# Buck_Converter_Board.net
KiCad netlist of a schematic drawn in EAGLE
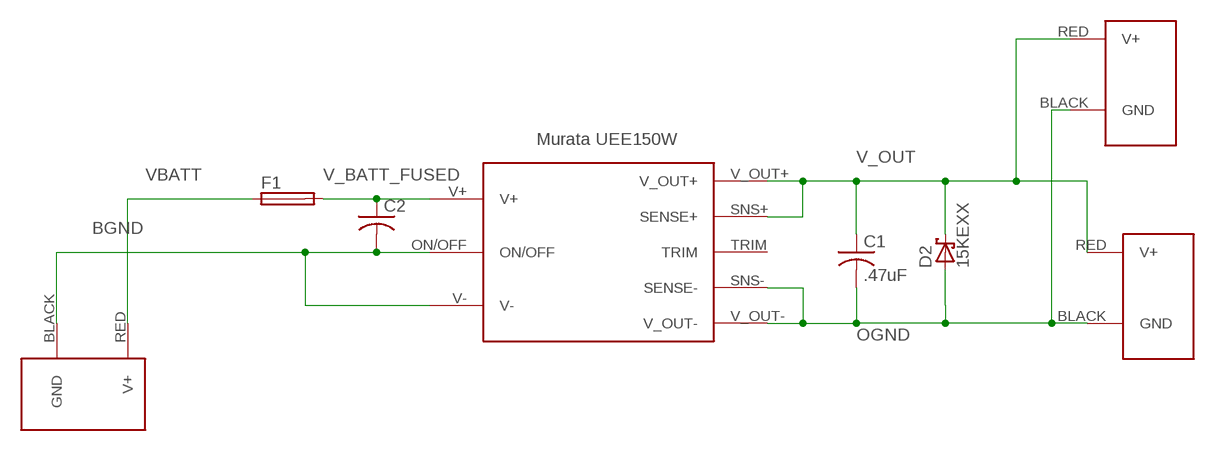
[diagram p0: schematic, sheet 1]

(export (version "E")
  (design (tool "Eeschema 10.0.6"))
  (components
    (comp (ref "C1")
      (value ".47uF")
      (footprint "eagle-import:C0805")
      (libsource (lib "eagle-import") (part "C-USC0805"))
    )
    (comp (ref "C2")
      (value "C-USC0805")
      (footprint "eagle-import:C0805")
      (libsource (lib "eagle-import") (part "C-USC0805"))
    )
    (comp (ref "D2")
      (value "15KEXX")
      (footprint "eagle-import:CB429-17")
      (libsource (lib "eagle-import") (part "15KEXX"))
    )
    (comp (ref "F1")
      (value "FUSEBLANK_5X20MM")
      (footprint "eagle-import:FUSE_HOLDER_5X20MM")
      (libsource (lib "eagle-import") (part "FUSEBLANK_5X20MM"))
    )
    (comp (ref "J1")
      (value "POWERPOLE_POWER25A_HORIZONTAL_G2")
      (footprint "eagle-import:POWERPOLE_PAIR_25A_HORIZ_G2")
      (libsource (lib "eagle-import") (part "POWERPOLE_POWER25A_HORIZONTAL_G2"))
    )
    (comp (ref "J2")
      (value "POWERPOLE_POWER25A_HORIZONTAL_G2")
      (footprint "eagle-import:POWERPOLE_PAIR_25A_HORIZ_G2")
      (libsource (lib "eagle-import") (part "POWERPOLE_POWER25A_HORIZONTAL_G2"))
    )
    (comp (ref "J3")
      (value "POWERPOLE_POWER25A_HORIZONTAL_G2")
      (footprint "eagle-import:POWERPOLE_PAIR_25A_HORIZ_G2")
      (libsource (lib "eagle-import") (part "POWERPOLE_POWER25A_HORIZONTAL_G2"))
    )
    (comp (ref "UEE150W")
      (value "UEE150W")
      (footprint "eagle-import:DOSA1_8")
      (libsource (lib "eagle-import") (part "UEE150W"))
    )
  )
  (nets
    (net (code "1") (name "/BGND") (class "Default")
      (node (ref "C2") (pin "2") (pinfunction "2_2") (pintype "passive"))
      (node (ref "J1") (pin "BLACK") (pinfunction "GND_BLACK") (pintype "power_in"))
      (node (ref "UEE150W") (pin "ON/OFF") (pinfunction "ON/OFF_ON/OFF") (pintype "input"))
      (node (ref "UEE150W") (pin "V-") (pinfunction "V-_V-") (pintype "power_in"))
    )
    (net (code "2") (name "/OGND") (class "Default")
      (node (ref "C1") (pin "2") (pinfunction "2_2") (pintype "passive"))
      (node (ref "D2") (pin "A") (pinfunction "A_A") (pintype "passive"))
      (node (ref "J2") (pin "BLACK") (pinfunction "GND_BLACK") (pintype "power_in"))
      (node (ref "J3") (pin "BLACK") (pinfunction "GND_BLACK") (pintype "power_in"))
      (node (ref "UEE150W") (pin "SNS-") (pinfunction "SENSE-_SNS-") (pintype "bidirectional"))
      (node (ref "UEE150W") (pin "V_OUT-") (pinfunction "V_OUT-_V_OUT-") (pintype "output"))
    )
    (net (code "3") (name "/VBATT") (class "Default")
      (node (ref "F1") (pin "1") (pinfunction "1_1") (pintype "passive"))
      (node (ref "J1") (pin "RED") (pinfunction "V+_RED") (pintype "power_in"))
    )
    (net (code "4") (name "/V_BATT_FUSED") (class "Default")
      (node (ref "C2") (pin "1") (pinfunction "1_1") (pintype "passive"))
      (node (ref "F1") (pin "2") (pinfunction "2_2") (pintype "passive"))
      (node (ref "UEE150W") (pin "V+") (pinfunction "V+_V+") (pintype "power_in"))
    )
    (net (code "5") (name "/V_OUT") (class "Default")
      (node (ref "C1") (pin "1") (pinfunction "1_1") (pintype "passive"))
      (node (ref "D2") (pin "C") (pinfunction "C_C") (pintype "passive"))
      (node (ref "J2") (pin "RED") (pinfunction "V+_RED") (pintype "power_in"))
      (node (ref "J3") (pin "RED") (pinfunction "V+_RED") (pintype "power_in"))
      (node (ref "UEE150W") (pin "SNS+") (pinfunction "SENSE+_SNS+") (pintype "bidirectional"))
      (node (ref "UEE150W") (pin "V_OUT+") (pinfunction "V_OUT+_V_OUT+") (pintype "output"))
    )
    (net (code "6") (name "unconnected-(UEE150W-PadTRIM)") (class "Default")
      (node (ref "UEE150W") (pin "TRIM") (pinfunction "TRIM_TRIM") (pintype "input"))
    )
  )
)
